# Lightbar.net
KiCad netlist of a schematic drawn in EAGLE
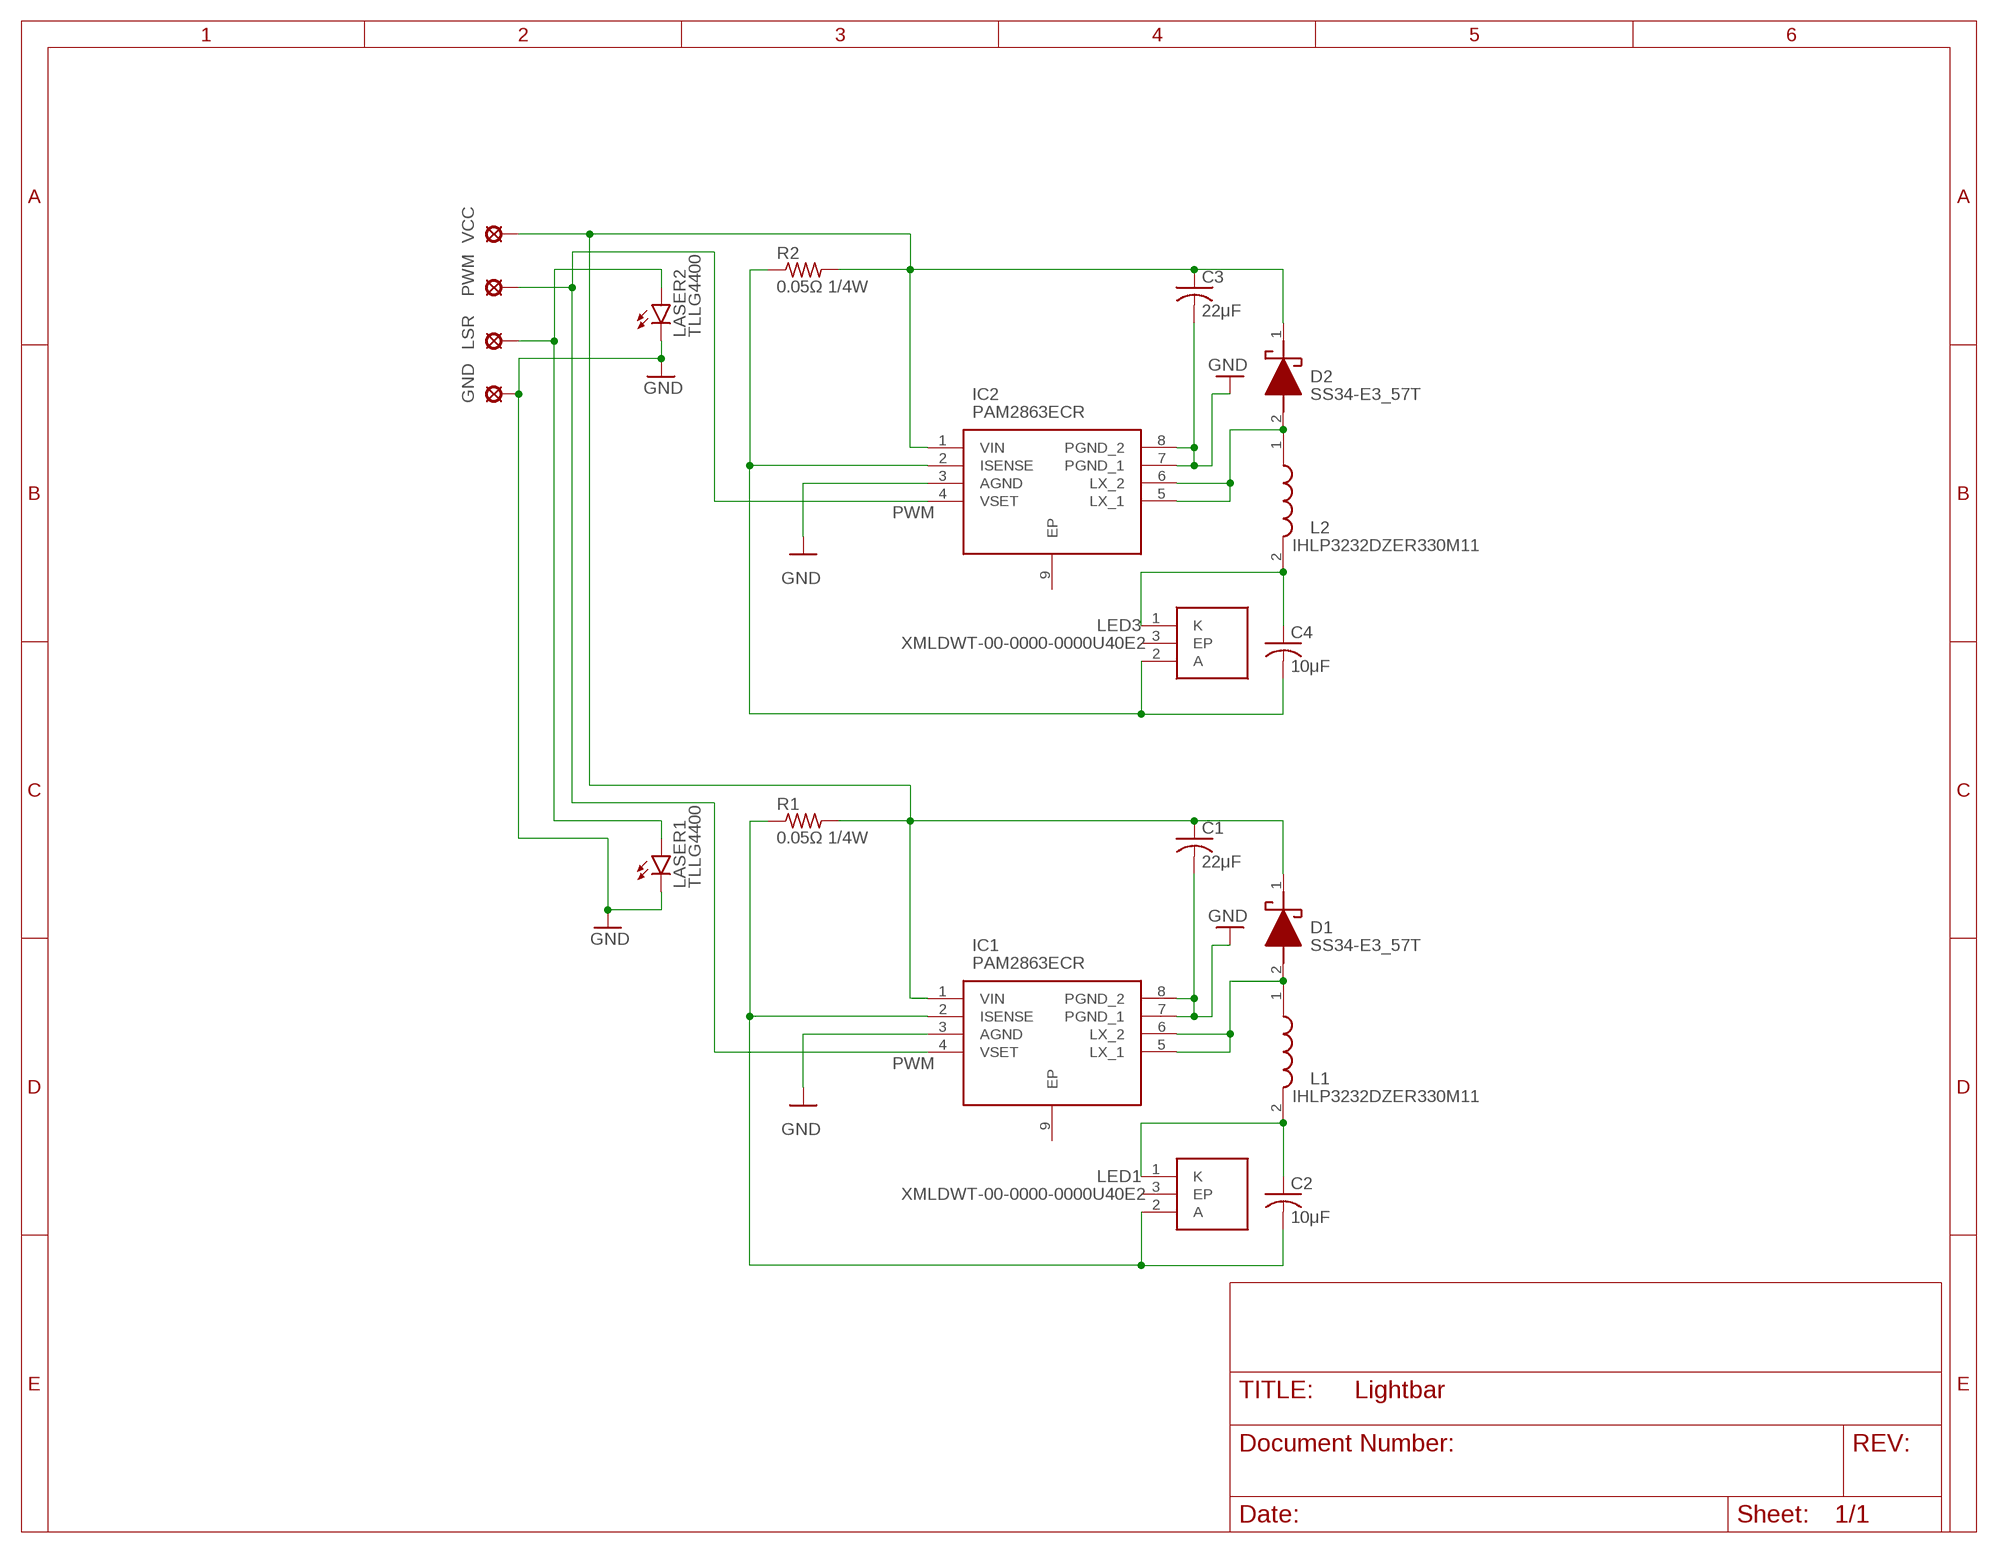
[diagram p0: schematic, sheet 1]

(export (version "E")
  (design (tool "Eeschema 10.0.6"))
  (components
    (comp (ref "C1")
      (value "22μF")
      (footprint "eagle-import:C1210")
      (libsource (lib "eagle-import") (part "C-USC1210"))
    )
    (comp (ref "C2")
      (value "10μF")
      (footprint "eagle-import:C1210")
      (libsource (lib "eagle-import") (part "C-USC1210"))
    )
    (comp (ref "C3")
      (value "22μF")
      (footprint "eagle-import:C1210")
      (libsource (lib "eagle-import") (part "C-USC1210"))
    )
    (comp (ref "C4")
      (value "10μF")
      (footprint "eagle-import:C1210")
      (libsource (lib "eagle-import") (part "C-USC1210"))
    )
    (comp (ref "D1")
      (value "SS34-E3_57T")
      (footprint "eagle-import:DIOM7959X262N")
      (fields
        (field (name "MANUFACTURER_PART_NUMBER") "SS34-E3/57T")
        (field (name "MOUSER_PART_NUMBER") "625-SS34-E3")
      )
      (libsource (lib "eagle-import") (part "SS34-E3_57T"))
    )
    (comp (ref "D2")
      (value "SS34-E3_57T")
      (footprint "eagle-import:DIOM7959X262N")
      (fields
        (field (name "MANUFACTURER_PART_NUMBER") "SS34-E3/57T")
        (field (name "MOUSER_PART_NUMBER") "625-SS34-E3")
      )
      (libsource (lib "eagle-import") (part "SS34-E3_57T"))
    )
    (comp (ref "GND")
      (value "LSP10")
      (footprint "eagle-import:LSP10")
      (libsource (lib "eagle-import") (part "LSP10"))
    )
    (comp (ref "IC1")
      (value "PAM2863ECR")
      (footprint "eagle-import:SOIC127P600X175-9N")
      (fields (field (name "MOUSER_PART_NUMBER") "621-PAM2863ECR"))
      (libsource (lib "eagle-import") (part "PAM2863ECR"))
    )
    (comp (ref "IC2")
      (value "PAM2863ECR")
      (footprint "eagle-import:SOIC127P600X175-9N")
      (fields (field (name "MOUSER_PART_NUMBER") "621-PAM2863ECR"))
      (libsource (lib "eagle-import") (part "PAM2863ECR"))
    )
    (comp (ref "L1")
      (value "IHLP3232DZER330M11")
      (footprint "eagle-import:IHLP3232DZER330M11")
      (fields (field (name "MOUSER_PART_NUMBER") "70-IHLP3232DZER330M1"))
      (libsource (lib "eagle-import") (part "IHLP3232DZER330M11"))
    )
    (comp (ref "L2")
      (value "IHLP3232DZER330M11")
      (footprint "eagle-import:IHLP3232DZER330M11")
      (fields (field (name "MOUSER_PART_NUMBER") "70-IHLP3232DZER330M1"))
      (libsource (lib "eagle-import") (part "IHLP3232DZER330M11"))
    )
    (comp (ref "LASER1")
      (value "TLLG4400")
      (footprint "eagle-import:LED3MM")
      (fields (field (name "MF") "VISHAY SEMICONDUCTOR"))
      (libsource (lib "eagle-import") (part "TLLG4400"))
    )
    (comp (ref "LASER2")
      (value "TLLG4400")
      (footprint "eagle-import:LED3MM")
      (fields (field (name "MF") "VISHAY SEMICONDUCTOR"))
      (libsource (lib "eagle-import") (part "TLLG4400"))
    )
    (comp (ref "LED1")
      (value "XMLDWT-00-0000-0000U40E2")
      (footprint "eagle-import:XMLDWT0000000000U40E2")
      (fields (field (name "MOUSER_PART_NUMBER") "941-XMLDWT0000U40E2"))
      (libsource (lib "eagle-import") (part "XMLDWT-00-0000-0000U40E2"))
    )
    (comp (ref "LED3")
      (value "XMLDWT-00-0000-0000U40E2")
      (footprint "eagle-import:XMLDWT0000000000U40E2")
      (fields (field (name "MOUSER_PART_NUMBER") "941-XMLDWT0000U40E2"))
      (libsource (lib "eagle-import") (part "XMLDWT-00-0000-0000U40E2"))
    )
    (comp (ref "LSR")
      (value "LSP10")
      (footprint "eagle-import:LSP10")
      (libsource (lib "eagle-import") (part "LSP10"))
    )
    (comp (ref "PWM")
      (value "LSP10")
      (footprint "eagle-import:LSP10")
      (libsource (lib "eagle-import") (part "LSP10"))
    )
    (comp (ref "R1")
      (value "0.05Ω 1/4W")
      (footprint "eagle-import:R0805")
      (libsource (lib "eagle-import") (part "R-US_R0805"))
    )
    (comp (ref "R2")
      (value "0.05Ω 1/4W")
      (footprint "eagle-import:R0805")
      (libsource (lib "eagle-import") (part "R-US_R0805"))
    )
    (comp (ref "VCC")
      (value "LSP10")
      (footprint "eagle-import:LSP10")
      (libsource (lib "eagle-import") (part "LSP10"))
    )
  )
  (nets
    (net (code "1") (name "GND") (class "Default")
      (node (ref "C1") (pin "2") (pinfunction "2_2") (pintype "passive"))
      (node (ref "C3") (pin "2") (pinfunction "2_2") (pintype "passive"))
      (node (ref "GND") (pin "MP") (pinfunction "MP_MP") (pintype "passive"))
      (node (ref "IC1") (pin "3") (pinfunction "AGND_3") (pintype "bidirectional"))
      (node (ref "IC1") (pin "7") (pinfunction "PGND_1_7") (pintype "bidirectional"))
      (node (ref "IC1") (pin "8") (pinfunction "PGND_2_8") (pintype "bidirectional"))
      (node (ref "IC2") (pin "3") (pinfunction "AGND_3") (pintype "bidirectional"))
      (node (ref "IC2") (pin "7") (pinfunction "PGND_1_7") (pintype "bidirectional"))
      (node (ref "IC2") (pin "8") (pinfunction "PGND_2_8") (pintype "bidirectional"))
      (node (ref "LASER1") (pin "K") (pinfunction "C_K") (pintype "passive"))
      (node (ref "LASER2") (pin "K") (pinfunction "C_K") (pintype "passive"))
    )
    (net (code "2") (name "Net-(D1-A)") (class "Default")
      (node (ref "D1") (pin "2") (pinfunction "A_2") (pintype "bidirectional"))
      (node (ref "IC1") (pin "5") (pinfunction "LX_1_5") (pintype "bidirectional"))
      (node (ref "IC1") (pin "6") (pinfunction "LX_2_6") (pintype "bidirectional"))
      (node (ref "L1") (pin "1") (pinfunction "1_1") (pintype "bidirectional"))
    )
    (net (code "3") (name "Net-(D1-K)") (class "Default")
      (node (ref "C1") (pin "1") (pinfunction "1_1") (pintype "passive"))
      (node (ref "C3") (pin "1") (pinfunction "1_1") (pintype "passive"))
      (node (ref "D1") (pin "1") (pinfunction "K_1") (pintype "bidirectional"))
      (node (ref "D2") (pin "1") (pinfunction "K_1") (pintype "bidirectional"))
      (node (ref "IC1") (pin "1") (pinfunction "VIN_1") (pintype "bidirectional"))
      (node (ref "IC2") (pin "1") (pinfunction "VIN_1") (pintype "bidirectional"))
      (node (ref "R1") (pin "2") (pinfunction "2_2") (pintype "passive"))
      (node (ref "R2") (pin "2") (pinfunction "2_2") (pintype "passive"))
      (node (ref "VCC") (pin "MP") (pinfunction "MP_MP") (pintype "passive"))
    )
    (net (code "4") (name "Net-(D2-A)") (class "Default")
      (node (ref "D2") (pin "2") (pinfunction "A_2") (pintype "bidirectional"))
      (node (ref "IC2") (pin "5") (pinfunction "LX_1_5") (pintype "bidirectional"))
      (node (ref "IC2") (pin "6") (pinfunction "LX_2_6") (pintype "bidirectional"))
      (node (ref "L2") (pin "1") (pinfunction "1_1") (pintype "bidirectional"))
    )
    (net (code "5") (name "Net-(IC1-ISENSE)") (class "Default")
      (node (ref "C2") (pin "2") (pinfunction "2_2") (pintype "passive"))
      (node (ref "IC1") (pin "2") (pinfunction "ISENSE_2") (pintype "bidirectional"))
      (node (ref "LED1") (pin "2") (pinfunction "A_2") (pintype "bidirectional"))
      (node (ref "R1") (pin "1") (pinfunction "1_1") (pintype "passive"))
    )
    (net (code "6") (name "Net-(IC1-VSET)") (class "Default")
      (node (ref "IC1") (pin "4") (pinfunction "VSET_4") (pintype "bidirectional"))
      (node (ref "IC2") (pin "4") (pinfunction "VSET_4") (pintype "bidirectional"))
      (node (ref "PWM") (pin "MP") (pinfunction "MP_MP") (pintype "passive"))
    )
    (net (code "7") (name "Net-(IC2-ISENSE)") (class "Default")
      (node (ref "C4") (pin "2") (pinfunction "2_2") (pintype "passive"))
      (node (ref "IC2") (pin "2") (pinfunction "ISENSE_2") (pintype "bidirectional"))
      (node (ref "LED3") (pin "2") (pinfunction "A_2") (pintype "bidirectional"))
      (node (ref "R2") (pin "1") (pinfunction "1_1") (pintype "passive"))
    )
    (net (code "8") (name "Net-(LASER1-PadA)") (class "Default")
      (node (ref "LASER1") (pin "A") (pinfunction "A_A") (pintype "passive"))
      (node (ref "LASER2") (pin "A") (pinfunction "A_A") (pintype "passive"))
      (node (ref "LSR") (pin "MP") (pinfunction "MP_MP") (pintype "passive"))
    )
    (net (code "9") (name "Net-(LED1-K)") (class "Default")
      (node (ref "C2") (pin "1") (pinfunction "1_1") (pintype "passive"))
      (node (ref "L1") (pin "2") (pinfunction "2_2") (pintype "bidirectional"))
      (node (ref "LED1") (pin "1") (pinfunction "K_1") (pintype "bidirectional"))
    )
    (net (code "10") (name "Net-(LED3-K)") (class "Default")
      (node (ref "C4") (pin "1") (pinfunction "1_1") (pintype "passive"))
      (node (ref "L2") (pin "2") (pinfunction "2_2") (pintype "bidirectional"))
      (node (ref "LED3") (pin "1") (pinfunction "K_1") (pintype "bidirectional"))
    )
    (net (code "11") (name "unconnected-(IC1-EP-Pad9)") (class "Default")
      (node (ref "IC1") (pin "9") (pinfunction "EP_9") (pintype "bidirectional"))
    )
    (net (code "12") (name "unconnected-(IC2-EP-Pad9)") (class "Default")
      (node (ref "IC2") (pin "9") (pinfunction "EP_9") (pintype "bidirectional"))
    )
    (net (code "13") (name "unconnected-(LED1-EP-Pad3)") (class "Default")
      (node (ref "LED1") (pin "3") (pinfunction "EP_3") (pintype "bidirectional"))
    )
    (net (code "14") (name "unconnected-(LED3-EP-Pad3)") (class "Default")
      (node (ref "LED3") (pin "3") (pinfunction "EP_3") (pintype "bidirectional"))
    )
  )
)
